# 002-0081_Rev_-.net
KiCad netlist of a schematic drawn in Altium Designer
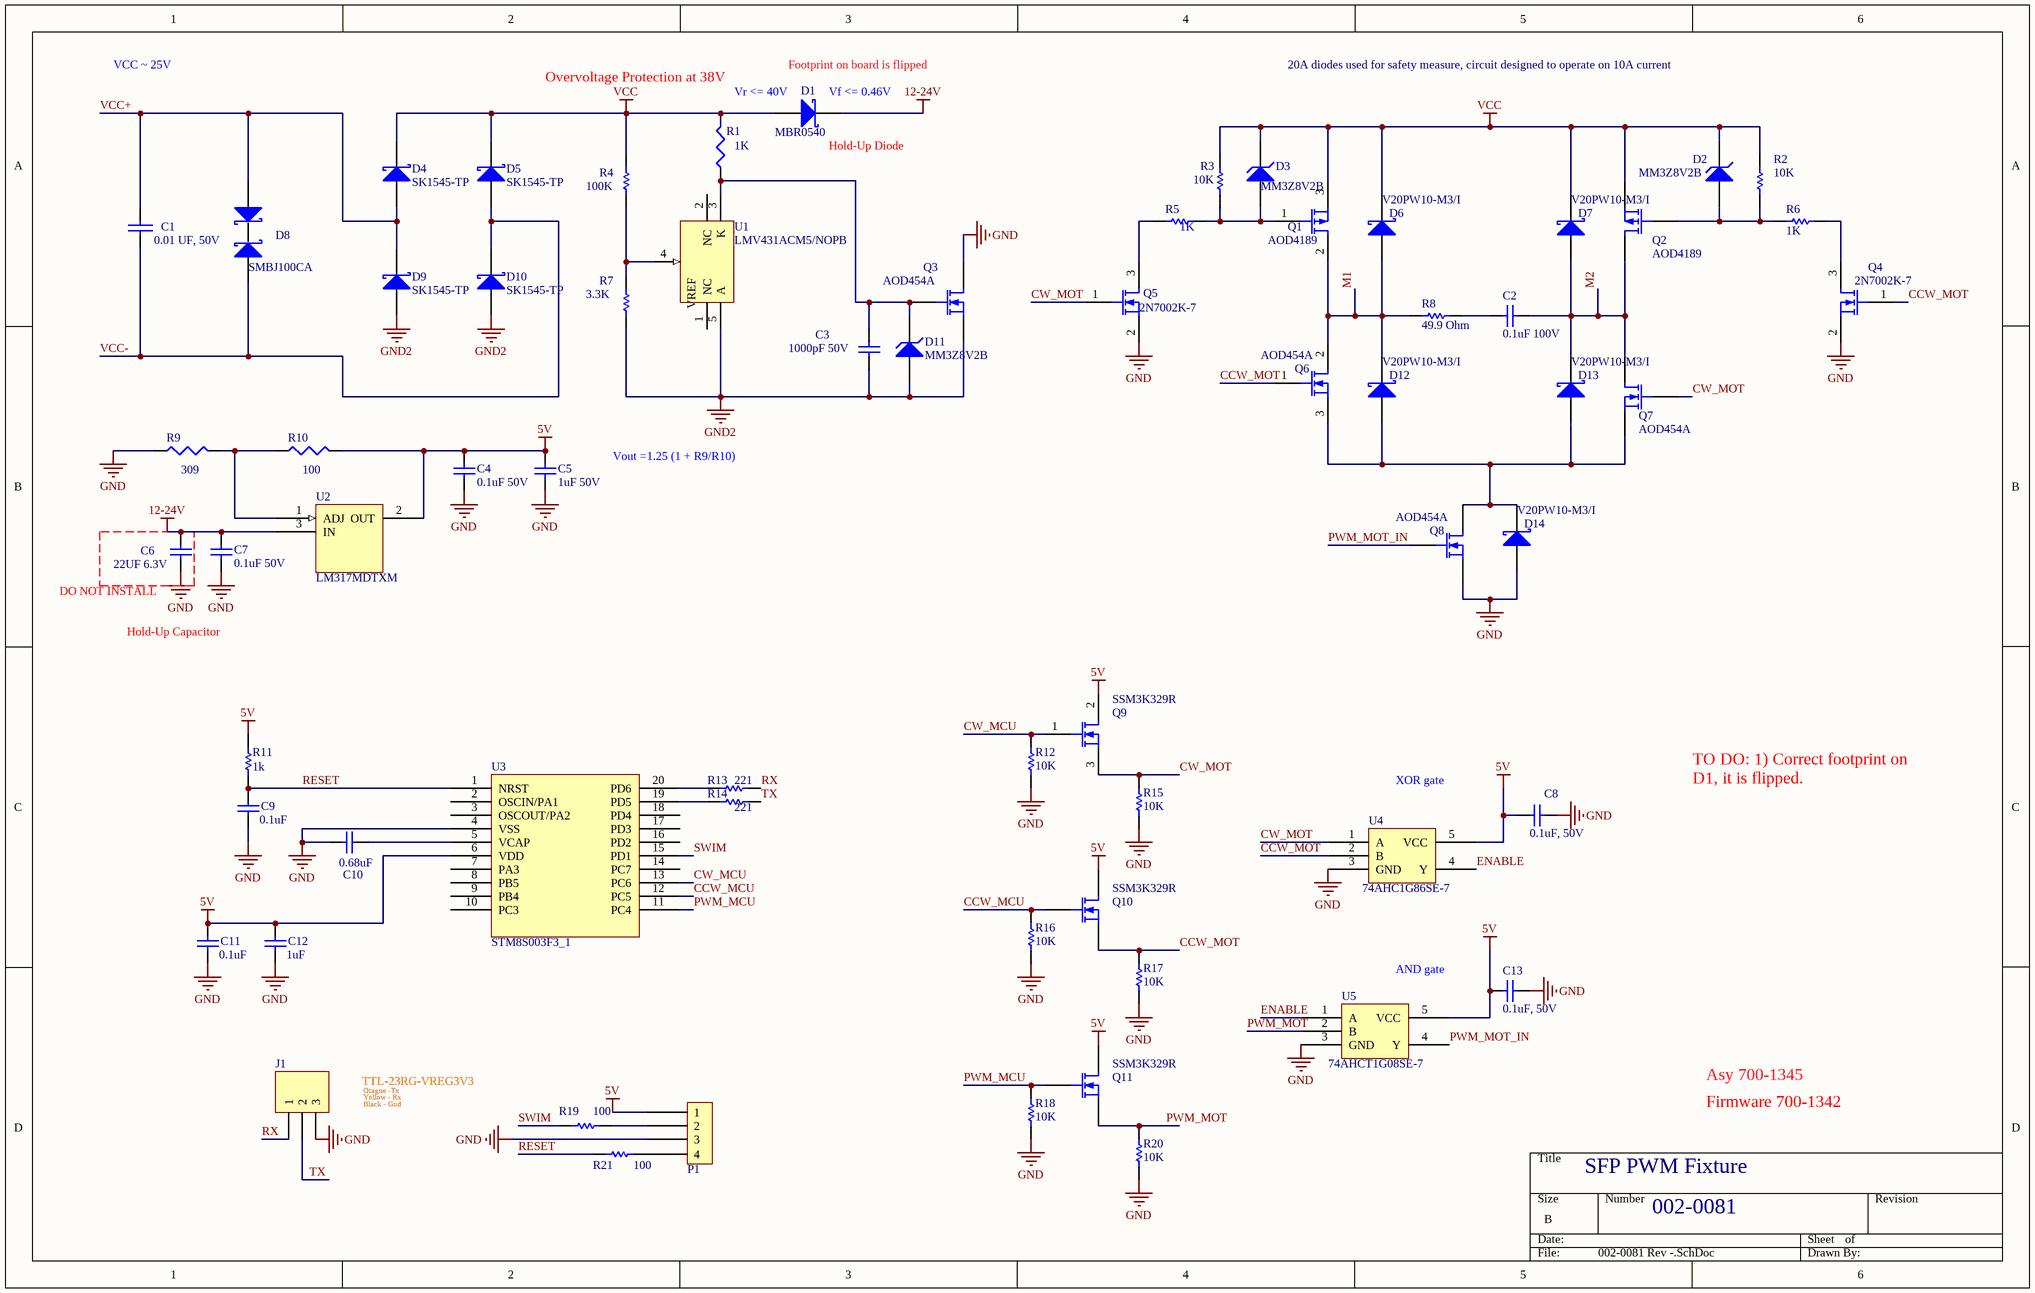
[diagram p0: 002-0081 Rev -.SchDoc]

(export (version "E")
  (design (tool "Eeschema 10.0.6"))
  (components
    (comp (ref "C1")
      (value "0.01 UF, 50V")
      (footprint "0603")
      (description "Cap Cer .01uf 50V 0603 RoHS")
      (fields
        (field (name "PEM PART NUMBER") "EE-1293")
        (field (name "MANUFACTURER") "Garrett Electronics Corporation")
      )
      (libsource (lib "*") (part "CAP"))
    )
    (comp (ref "C2")
      (value "0.1uF 100V")
      (footprint "RESC0805(2012)_N")
      (description "Cap Cer 0.1uF 100V 10% X7R 0805")
      (fields (field (name "PART NUMBER") "CL21B104KCFSFNE") (field (name "PEM PART NUMBER") "EE-1659"))
      (libsource (lib "Miscellaneous Devices") (part "Cap"))
    )
    (comp (ref "C3")
      (value "1000pF 50V")
      (footprint "0603")
      (description "CAP Cer, 0.1uF, 50V, 0603 X7R, 10%")
      (fields
        (field (name "MANUFACTURER PART NUMBER") "06035C104KAT2A")
        (field (name "PEM PART NUMBER") "EE-1343")
      )
      (libsource (lib "Miscellaneous Devices") (part "Cap"))
    )
    (comp (ref "C4")
      (value "0.1uF 50V")
      (footprint "0603")
      (description "CAP Cer, 0.1uF, 50V, 0603 X7R, 10%")
      (fields
        (field (name "MANUFACTURER PART NUMBER") "06035C104KAT2A")
        (field (name "PEM PART NUMBER") "EE-1425")
      )
      (libsource (lib "Miscellaneous Devices") (part "Cap"))
    )
    (comp (ref "C5")
      (value "1uF 50V")
      (footprint "0603")
      (description "CAP CER 1UF 50V 10% X5R 0603")
      (fields
        (field (name "MANUFACTURER PART NUMBER") "06035C104KAT2A")
        (field (name "PEM PART NUMBER") "EE-1708")
      )
      (libsource (lib "Miscellaneous Devices") (part "Cap"))
    )
    (comp (ref "C6")
      (value "22UF 6.3V")
      (footprint "0603")
      (description "CAP CER 22UF 6.3V X5R 0603")
      (fields
        (field (name "MANUFACTURER PART NUMBER") "06035C104KAT2A")
        (field (name "PEM PART NUMBER") "EE-1981")
      )
      (libsource (lib "Miscellaneous Devices") (part "Cap"))
    )
    (comp (ref "C7")
      (value "0.1uF 50V")
      (footprint "0603")
      (description "CAP Cer, 0.1uF, 50V, 0603 X7R, 10%")
      (fields
        (field (name "MANUFACTURER PART NUMBER") "06035C104KAT2A")
        (field (name "PEM PART NUMBER") "EE-1425")
      )
      (libsource (lib "Miscellaneous Devices") (part "Cap"))
    )
    (comp (ref "C8")
      (value "0.1uF, 50V")
      (footprint "0603")
      (description "CAP Cer, 0.1uF, 50V, 0603 X7R, 10%")
      (fields (field (name "PEM PART NUMBER") "EE-1425") (field (name "PART NUMBER") "06035C104KAT2A"))
      (libsource (lib "Miscellaneous Devices") (part "Cap"))
    )
    (comp (ref "C9")
      (value "0.1uF")
      (footprint "CAPC0402(1005)60_M")
      (description "Cap Cer 0.1uF 10V 10% X5R 0402")
      (fields (field (name "PART NUMBER") "LMK105BJ104KV-F") (field (name "PEM PART NUMBER") "EE-1661"))
      (libsource (lib "Miscellaneous Devices") (part "Cap"))
    )
    (comp (ref "C10")
      (value "0.68uF")
      (footprint "CAPC0402(1005)60_M")
      (description "Cap cer 0.68uF 6.3V 5% X6S 0402")
      (fields (field (name "PEM PART NUMBER") "EE-1673") (field (name "PART NUMBER") "CL05X684JQ5NNNC"))
      (libsource (lib "Miscellaneous Devices") (part "Cap"))
    )
    (comp (ref "C11")
      (value "0.1uF")
      (footprint "CAPC0402(1005)60_M")
      (description "Cap Cer 0.1uF 10V 10% X5R 0402")
      (fields (field (name "PART NUMBER") "LMK105BJ104KV-F") (field (name "PEM PART NUMBER") "EE-1661"))
      (libsource (lib "Miscellaneous Devices") (part "Cap"))
    )
    (comp (ref "C12")
      (value "1uF")
      (footprint "CAPC0402(1005)60_M")
      (description "Cap Cer 1uF 10V 10% X5R 0402")
      (fields (field (name "PART NUMBER") "C1005X5R1V105M050BC") (field (name "PEM PART NUMBER") "EE-1725"))
      (libsource (lib "Miscellaneous Devices") (part "Cap"))
    )
    (comp (ref "C13")
      (value "0.1uF, 50V")
      (footprint "0603")
      (description "Cap Cer 0.1uF 10V 10% X5R 0402")
      (fields (field (name "PEM PART NUMBER") "EE-1425") (field (name "PART NUMBER") "06035C104KAT2A"))
      (libsource (lib "Miscellaneous Devices") (part "Cap"))
    )
    (comp (ref "D1")
      (value "MBR0540")
      (footprint "SOD123/X.85")
      (description "Diode Schottky 40V 500ma SOD-123")
      (fields
        (field (name "MANUFACTURER PART NUMBER") "MBR0540-TP")
        (field (name "PEM PART NUMBER") "EE-1290")
      )
      (libsource (lib "Miscellaneous Devices") (part "D Schottky"))
    )
    (comp (ref "D2")
      (value "MM3Z8V2B")
      (footprint "SOD-323F")
      (description "DIODE ZENER 8.2V 200MW SOD323F")
      (fields (field (name "PEM PART NUMBER") "EE-1681"))
      (libsource (lib "Miscellaneous Devices") (part "D Zener"))
    )
    (comp (ref "D3")
      (value "MM3Z8V2B")
      (footprint "SOD-323F")
      (description "DIODE ZENER 8.2V 200MW SOD323F")
      (fields (field (name "PEM PART NUMBER") "EE-1681"))
      (libsource (lib "Miscellaneous Devices") (part "D Zener"))
    )
    (comp (ref "D4")
      (value "SK1545-TP")
      (footprint "SMC")
      (description "DIODE SCHOTTKY 45V 15A DO214AB")
      (fields (field (name "PEM PART NUMBER") "EE-2167"))
      (libsource (lib "") (part "D Schottky_1"))
    )
    (comp (ref "D5")
      (value "SK1545-TP")
      (footprint "SMC")
      (description "DIODE SCHOTTKY 45V 15A DO214AB")
      (fields (field (name "PEM PART NUMBER") "EE-2167"))
      (libsource (lib "") (part "D Schottky_1"))
    )
    (comp (ref "D6")
      (value "V20PW10-M3/I")
      (footprint "DPAK (TO-252-3)")
      (description "DIODE SCHOTTKY 100V 20A SLIMDPAK")
      (fields (field (name "PEM PART NUMBER") "EE-2166"))
      (libsource (lib "") (part "D Schottky_1"))
    )
    (comp (ref "D7")
      (value "V20PW10-M3/I")
      (footprint "DPAK (TO-252-3)")
      (description "DIODE SCHOTTKY 100V 20A SLIMDPAK")
      (fields (field (name "PEM PART NUMBER") "EE-2166"))
      (libsource (lib "") (part "D Schottky_1"))
    )
    (comp (ref "D8")
      (value "TVS DIODE 28VWM 45.4VC SMB")
      (footprint "SMB - Bidirection")
      (description "TVS DIODE 100VWM 162VC DO214AA")
      (fields
        (field (name "PART NUMBER") "SMBJ100CA")
        (field (name "MANUFACTURER") "ON Semiconductor")
        (field (name "PEM PART NUMBER") "EE-1946")
      )
      (libsource (lib "002-0017 Rev H") (part "Dual Zener"))
    )
    (comp (ref "D9")
      (value "SK1545-TP")
      (footprint "SMC")
      (description "DIODE SCHOTTKY 45V 15A DO214AB")
      (fields (field (name "PEM PART NUMBER") "EE-2167"))
      (libsource (lib "") (part "D Schottky_1"))
    )
    (comp (ref "D10")
      (value "SK1545-TP")
      (footprint "SMC")
      (description "DIODE SCHOTTKY 45V 15A DO214AB")
      (fields (field (name "PEM PART NUMBER") "EE-2167"))
      (libsource (lib "") (part "D Schottky_1"))
    )
    (comp (ref "D11")
      (value "MM3Z8V2B")
      (footprint "SOD-323F")
      (description "DIODE ZENER 8.2V 200MW SOD323F")
      (fields (field (name "PEM PART NUMBER") "EE-1681"))
      (libsource (lib "Miscellaneous Devices") (part "D Zener"))
    )
    (comp (ref "D12")
      (value "V20PW10-M3/I")
      (footprint "DPAK (TO-252-3)")
      (description "DIODE SCHOTTKY 100V 20A SLIMDPAK")
      (fields (field (name "PEM PART NUMBER") "EE-2166"))
      (libsource (lib "") (part "D Schottky_1"))
    )
    (comp (ref "D13")
      (value "V20PW10-M3/I")
      (footprint "DPAK (TO-252-3)")
      (description "DIODE SCHOTTKY 100V 20A SLIMDPAK")
      (fields (field (name "PEM PART NUMBER") "EE-2166"))
      (libsource (lib "") (part "D Schottky_1"))
    )
    (comp (ref "D14")
      (value "V20PW10-M3/I")
      (footprint "DPAK (TO-252-3)")
      (description "DIODE SCHOTTKY 100V 20A SLIMDPAK")
      (fields (field (name "PEM PART NUMBER") "EE-2166"))
      (libsource (lib "") (part "D Schottky_1"))
    )
    (comp (ref "J1")
      (value "RS232 Conn")
      (footprint "SCON3/.10")
      (description "CONN HDR VERT 3POS .100 TIN")
      (fields
        (field (name "PEM PART NUMBER") "EE-1116")
        (field (name "MANUFACTURER") "Phoenix Contact")
        (field (name "PUBLISHER") "Altium Limited")
      )
      (libsource (lib "Miscellaneous Connectors") (part "Header 3"))
    )
    (comp (ref "P1")
      (value "4 Pin Connector")
      (footprint "4 PIN IN-LINE")
      (fields
        (field (name "PEM PART NUMBER") "EE-1855")
        (field (name "PART NUMBER") "GRPB501VWVN-RC")
        (field (name "MANUFACTURER") "Sullins Connector Solutions")
      )
      (libsource (lib "002 - 0053 Rev A") (part "4 Pin Connector"))
    )
    (comp (ref "Q1")
      (value "AOD4189")
      (footprint "DPAK (TO-252-3)")
      (description "MOSFET P-CH 40V 40A TO252 DPAK")
      (fields (field (name "PEM PART NUMBER") "EE-1879"))
      (libsource (lib "") (part "MOSFET-P_1"))
    )
    (comp (ref "Q2")
      (value "AOD4189")
      (footprint "DPAK (TO-252-3)")
      (description "MOSFET P-CH 40V 40A TO252 DPAK")
      (fields (field (name "PEM PART NUMBER") "EE-1879"))
      (libsource (lib "Miscellaneous Devices") (part "MOSFET-P"))
    )
    (comp (ref "Q3")
      (value "AOD454A")
      (footprint "DPAK (TO-252-3)")
      (description "MOSFET N-CH 250V 16A D-PAK")
      (fields (field (name "PEM PART NUMBER") "EE-1898"))
      (libsource (lib "") (part "MOSFET-N_1"))
    )
    (comp (ref "Q4")
      (value "2N7002K-7")
      (footprint "SOT-23-3")
      (description "MOSFET N-CH 60V 0.38A SOT23-3")
      (fields (field (name "PEM PART NUMBER") "EE-2053"))
      (libsource (lib "") (part "MOSFET-N_2"))
    )
    (comp (ref "Q5")
      (value "2N7002K-7")
      (footprint "SOT-23-3")
      (description "MOSFET N-CH 60V 0.38A SOT23-3")
      (fields (field (name "PEM PART NUMBER") "EE-2053"))
      (libsource (lib "") (part "MOSFET-N_2"))
    )
    (comp (ref "Q6")
      (value "AOD454A")
      (footprint "DPAK (TO-252-3)")
      (description "MOSFET N-CH 40V 20A TO252")
      (fields
        (field (name "MANUFACTURER") "Alpha & Omega Semiconductor Inc.")
        (field (name "PEM PART NUMBER") "EE-1898")
      )
      (libsource (lib "Miscellaneous Devices") (part "MOSFET-N"))
    )
    (comp (ref "Q7")
      (value "AOD454A")
      (footprint "DPAK (TO-252-3)")
      (description "MOSFET N-CH 40V 20A TO252")
      (fields
        (field (name "MANUFACTURER") "Alpha & Omega Semiconductor Inc.")
        (field (name "PEM PART NUMBER") "EE-1898")
      )
      (libsource (lib "") (part "MOSFET-N_1"))
    )
    (comp (ref "Q8")
      (value "AOD454A")
      (footprint "DPAK (TO-252-3)")
      (description "MOSFET N-CH 40V 20A TO252")
      (fields
        (field (name "MANUFACTURER") "Alpha & Omega Semiconductor Inc.")
        (field (name "PEM PART NUMBER") "EE-1898")
      )
      (libsource (lib "") (part "MOSFET-N_1"))
    )
    (comp (ref "Q9")
      (value "SSM3K329R")
      (footprint "SOT-23F")
      (description "N-Channel 30V 3.5A (Ta) 1W (Ta) Surface Mount SOT-23F")
      (fields
        (field (name "MANUFACTURER") "Alpha & Omega Semiconductor Inc.")
        (field (name "PEM PART NUMBER") "EE-1830")
      )
      (libsource (lib "Miscellaneous Devices") (part "MOSFET-N"))
    )
    (comp (ref "Q10")
      (value "SSM3K329R")
      (footprint "SOT-23F")
      (description "N-Channel 30V 3.5A (Ta) 1W (Ta) Surface Mount SOT-23F")
      (fields
        (field (name "MANUFACTURER") "Alpha & Omega Semiconductor Inc.")
        (field (name "PEM PART NUMBER") "EE-1830")
      )
      (libsource (lib "") (part "MOSFET-N_1"))
    )
    (comp (ref "Q11")
      (value "SSM3K329R")
      (footprint "SOT-23F")
      (description "N-Channel 30V 3.5A (Ta) 1W (Ta) Surface Mount SOT-23F")
      (fields
        (field (name "PART NUMBER") "AOD454A")
        (field (name "MANUFACTURER") "Alpha & Omega Semiconductor Inc.")
      )
      (libsource (lib "") (part "MOSFET-N_1"))
    )
    (comp (ref "R1")
      (value "1K")
      (footprint "002-0081 Rev -:RESC0603(1608)_M")
      (description "RES SMD 1K OHM 1% 1/10W 0603")
      (fields
        (field (name "PEM PART NUMBER") "EE-2066")
        (field (name "Comment") "Res3")
        (field (name "PUBLISHER") "Altium Limited")
      )
      (libsource (lib "Miscellaneous Devices") (part "Res3"))
    )
    (comp (ref "R2")
      (value "10K")
      (footprint "RESC0603(1608)_M")
      (description "Res 10K 0603 1% 1/10W RoHS")
      (fields (field (name "PART NUMBER") "RK73H1JTTD1002F") (field (name "PEM PART NUMBER") "EE-1296"))
      (libsource (lib "Miscellaneous Devices") (part "Res1"))
    )
    (comp (ref "R3")
      (value "10K")
      (footprint "RESC0603(1608)_M")
      (description "Res 10K 0603 1% 1/10W RoHS")
      (fields (field (name "PART NUMBER") "RK73H1JTTD1002F") (field (name "PEM PART NUMBER") "EE-1296"))
      (libsource (lib "Miscellaneous Devices") (part "Res1"))
    )
    (comp (ref "R4")
      (value "100K")
      (footprint "RESC0603(1608)_M")
      (description "Res 100K 0603 1% 1/10W RoHS")
      (fields (field (name "PART NUMBER") "RK73H1JTTD1002F") (field (name "PEM PART NUMBER") "EE-1295"))
      (libsource (lib "Miscellaneous Devices") (part "Res1"))
    )
    (comp (ref "R5")
      (value "1K")
      (footprint "RESC0603(1608)_M")
      (description "Res 1.0K 0603 1% 1/10W RoHS")
      (fields
        (field (name "MANUFACTURER PART NUMBER") "CRCW06031K00FKEA")
        (field (name "PEM PART NUMBER") "EE-1297")
      )
      (libsource (lib "Miscellaneous Devices") (part "Res1"))
    )
    (comp (ref "R6")
      (value "1K")
      (footprint "RESC0603(1608)_M")
      (description "Res 1.0K 0603 1% 1/10W RoHS")
      (fields
        (field (name "MANUFACTURER PART NUMBER") "CRCW06031K00FKEA")
        (field (name "PEM PART NUMBER") "EE-1297")
      )
      (libsource (lib "Miscellaneous Devices") (part "Res1"))
    )
    (comp (ref "R7")
      (value "3.3K")
      (footprint "RESC0603(1608)_M")
      (description "RES 23.7K OHM 1/10W 1% 0603 SMD")
      (fields (field (name "PART NUMBER") "MCR03ERTF3301") (field (name "PEM PART NUMBER") "EE-1730"))
      (libsource (lib "Miscellaneous Devices") (part "Res1"))
    )
    (comp (ref "R8")
      (value "49.9 Ohm")
      (footprint "RESC0805(2012)_N")
      (description "Res 49.9R 0805 1% 1/8W")
      (fields (field (name "PEM PART NUMBER") "EE-1238") (field (name "PART NUMBER") "9C08052A49R9FKHFT"))
      (libsource (lib "Miscellaneous Devices") (part "Res1"))
    )
    (comp (ref "R9")
      (value "309")
      (footprint "J1-0603")
      (description "Res 10K 0603 1% 1/10W RoHS")
      (fields (field (name "PEM PART NUMBER") "EE-1296") (field (name "PART NUMBER") "RK73H1JTTD1002F"))
      (libsource (lib "Miscellaneous Devices") (part "Res3"))
    )
    (comp (ref "R10")
      (value "100")
      (footprint "J1-0603")
      (description "Res 3.3K 0603 1% 1/8W RoHS")
      (fields (field (name "PEM PART NUMBER") "EE-1730") (field (name "PART NUMBER") "MCR03ERTF3301"))
      (libsource (lib "Miscellaneous Devices") (part "Res3"))
    )
    (comp (ref "R11")
      (value "1k")
      (footprint "RESC0402(1005)_N")
      (description "Res 1K 0402 1% 1/16W RoHS")
      (fields (field (name "PEM PART NUMBER") "EE-1581") (field (name "PART NUMBER") "CRCW04021K00FKED"))
      (libsource (lib "Miscellaneous Devices") (part "Res1"))
    )
    (comp (ref "R12")
      (value "10K")
      (footprint "RESC0603(1608)_M")
      (description "Res 10K 0603 1% 1/10W RoHS")
      (fields (field (name "PART NUMBER") "RK73H1JTTD1002F") (field (name "PEM PART NUMBER") "EE-1296"))
      (libsource (lib "Miscellaneous Devices") (part "Res1"))
    )
    (comp (ref "R13")
      (value "221")
      (footprint "RESC0402(1005)_N")
      (description "RES SMD 221 OHM 1% 1/16W 0402")
      (fields (field (name "PART NUMBER") "RC1005F2210CS") (field (name "PEM PART NUMBER") "EE-1798"))
      (libsource (lib "Miscellaneous Devices") (part "Res1"))
    )
    (comp (ref "R14")
      (value "221")
      (footprint "RESC0402(1005)_N")
      (description "Res 1K 0603 1% 1/10W RoHS")
      (fields (field (name "PART NUMBER") "RC1005F2210CS") (field (name "PEM PART NUMBER") "EE-1798"))
      (libsource (lib "Miscellaneous Devices") (part "Res1"))
    )
    (comp (ref "R15")
      (value "10K")
      (footprint "RESC0603(1608)_M")
      (description "Res 10K 0603 1% 1/10W RoHS")
      (fields (field (name "PART NUMBER") "RK73H1JTTD1002F") (field (name "PEM PART NUMBER") "EE-1296"))
      (libsource (lib "Miscellaneous Devices") (part "Res1"))
    )
    (comp (ref "R16")
      (value "10K")
      (footprint "RESC0603(1608)_M")
      (description "Res 10K 0603 1% 1/10W RoHS")
      (fields (field (name "PART NUMBER") "RK73H1JTTD1002F") (field (name "PEM PART NUMBER") "EE-1296"))
      (libsource (lib "Miscellaneous Devices") (part "Res1"))
    )
    (comp (ref "R17")
      (value "10K")
      (footprint "RESC0603(1608)_M")
      (description "Res 10K 0603 1% 1/10W RoHS")
      (fields (field (name "PART NUMBER") "RK73H1JTTD1002F") (field (name "PEM PART NUMBER") "EE-1296"))
      (libsource (lib "Miscellaneous Devices") (part "Res1"))
    )
    (comp (ref "R18")
      (value "10K")
      (footprint "RESC0603(1608)_M")
      (description "Res 10K 0603 1% 1/10W RoHS")
      (fields (field (name "PART NUMBER") "RK73H1JTTD1002F") (field (name "PEM PART NUMBER") "EE-1296"))
      (libsource (lib "Miscellaneous Devices") (part "Res1"))
    )
    (comp (ref "R19")
      (value "100")
      (footprint "RESC0402(1005)_N")
      (description "Res 100R 0402 1% 1/16W RoHs")
      (fields (field (name "PEM PART NUMBER") "EE-1588") (field (name "PART NUMBER") "RC0402FR-07100RL"))
      (libsource (lib "Miscellaneous Devices") (part "Res1"))
    )
    (comp (ref "R20")
      (value "10K")
      (footprint "RESC0603(1608)_M")
      (description "Res 10K 0603 1% 1/10W RoHS")
      (fields (field (name "PART NUMBER") "RK73H1JTTD1002F") (field (name "PEM PART NUMBER") "EE-1296"))
      (libsource (lib "Miscellaneous Devices") (part "Res1"))
    )
    (comp (ref "R21")
      (value "100")
      (footprint "RESC0402(1005)_N")
      (description "Res 100R 0402 1% 1/16W RoHs")
      (fields (field (name "PEM PART NUMBER") "EE-1588") (field (name "PART NUMBER") "RC0402FR-07100RL"))
      (libsource (lib "Miscellaneous Devices") (part "Res1"))
    )
    (comp (ref "U1")
      (value "LMV431ACM5/NOPB")
      (footprint "DBV005")
      (description "IC VREF SHUNT ADJ SOT23-5")
      (fields (field (name "PEM PART NUMBER") "EE-1900"))
      (libsource (lib "TI Power Mgt Voltage Regulator") (part "TL431IDBVR"))
    )
    (comp (ref "U2")
      (value "LM317MDTXM")
      (footprint "DPAK (TO-252-3)")
      (description "SMT, IC, Adjust Voltage Reg, 0.5A, 3TERM, TO-252, 40V diff max")
      (fields
        (field (name "PEM PART NUMBER") "EE-1248")
        (field (name "MANUFACTURER") "Fairchild Semiconductor")
      )
      (libsource (lib "*") (part "LM317D2T(3)"))
    )
    (comp (ref "U3")
      (value "STM8S003F3_1")
      (footprint "UFQFPN20_V")
      (description "MCU 8BIT 8KB 16MHZ 20-UFQFPN")
      (fields (field (name "PEM PART NUMBER") "EE-1655") (field (name "PART NUMBER") "STM8S003F3U6TR"))
      (libsource (lib "SlowActuator") (part "STM8S003F3_1"))
    )
    (comp (ref "U4")
      (value "74AHC1G86SE-7")
      (footprint "SOT-353")
      (description "IC GATE XOR 1CH 2-INP SOT353")
      (fields (field (name "PEM PART NUMBER") "EE-2165") (field (name "MANUFACTURER") "Diodes Incorporated"))
      (libsource (lib "002-0066 Rev -") (part "NC7SZ08"))
    )
    (comp (ref "U5")
      (value "74AHCT1G08SE-7")
      (footprint "SOT-353")
      (description "IC GATE AND 1CH 2-INP SOT-353")
      (fields (field (name "PEM PART NUMBER") "EE-1801") (field (name "MANUFACTURER") "Diodes Incorporated"))
      (libsource (lib "002-0066 Rev -") (part "NC7SZ08"))
    )
  )
  (nets
    (net (code "1") (name "/CCW_MCU") (class "Default")
      (node (ref "Q10") (pin "1") (pinfunction "G_1") (pintype "passive"))
      (node (ref "R16") (pin "1") (pinfunction "1_1") (pintype "passive"))
      (node (ref "U3") (pin "12") (pinfunction "PC5_12") (pintype "passive"))
    )
    (net (code "2") (name "/CCW_MOT") (class "Default")
      (node (ref "Q10") (pin "3") (pinfunction "S_3") (pintype "passive"))
      (node (ref "Q4") (pin "1") (pinfunction "G_1") (pintype "passive"))
      (node (ref "Q6") (pin "1") (pinfunction "G_1") (pintype "passive"))
      (node (ref "R17") (pin "1") (pinfunction "1_1") (pintype "passive"))
      (node (ref "U4") (pin "2") (pinfunction "B_2") (pintype "passive"))
    )
    (net (code "3") (name "/CW_MCU") (class "Default")
      (node (ref "Q9") (pin "1") (pinfunction "G_1") (pintype "passive"))
      (node (ref "R12") (pin "1") (pinfunction "1_1") (pintype "passive"))
      (node (ref "U3") (pin "13") (pinfunction "PC6_13") (pintype "passive"))
    )
    (net (code "4") (name "/CW_MOT") (class "Default")
      (node (ref "Q5") (pin "1") (pinfunction "G_1") (pintype "passive"))
      (node (ref "Q7") (pin "1") (pinfunction "G_1") (pintype "passive"))
      (node (ref "Q9") (pin "3") (pinfunction "S_3") (pintype "passive"))
      (node (ref "R15") (pin "1") (pinfunction "1_1") (pintype "passive"))
      (node (ref "U4") (pin "1") (pinfunction "A_1") (pintype "passive"))
    )
    (net (code "5") (name "/ENABLE") (class "Default")
      (node (ref "U4") (pin "4") (pinfunction "Y_4") (pintype "passive"))
      (node (ref "U5") (pin "1") (pinfunction "A_1") (pintype "passive"))
    )
    (net (code "6") (name "/M1") (class "Default")
      (node (ref "D12") (pin "2") (pinfunction "K_2") (pintype "passive"))
      (node (ref "D6") (pin "1") (pinfunction "A_1") (pintype "passive"))
      (node (ref "Q1") (pin "2") (pinfunction "D_2") (pintype "passive"))
      (node (ref "Q6") (pin "2") (pinfunction "D_2") (pintype "passive"))
      (node (ref "R8") (pin "2") (pinfunction "2_2") (pintype "passive"))
    )
    (net (code "7") (name "/M2") (class "Default")
      (node (ref "C2") (pin "1") (pinfunction "1_1") (pintype "passive"))
      (node (ref "D13") (pin "2") (pinfunction "K_2") (pintype "passive"))
      (node (ref "D7") (pin "1") (pinfunction "A_1") (pintype "passive"))
      (node (ref "Q2") (pin "2") (pinfunction "D_2") (pintype "passive"))
      (node (ref "Q7") (pin "2") (pinfunction "D_2") (pintype "passive"))
    )
    (net (code "8") (name "/PWM_MCU") (class "Default")
      (node (ref "Q11") (pin "1") (pinfunction "G_1") (pintype "passive"))
      (node (ref "R18") (pin "1") (pinfunction "1_1") (pintype "passive"))
      (node (ref "U3") (pin "11") (pinfunction "PC4_11") (pintype "passive"))
    )
    (net (code "9") (name "/PWM_MOT") (class "Default")
      (node (ref "Q11") (pin "3") (pinfunction "S_3") (pintype "passive"))
      (node (ref "R20") (pin "1") (pinfunction "1_1") (pintype "passive"))
      (node (ref "U5") (pin "2") (pinfunction "B_2") (pintype "passive"))
    )
    (net (code "10") (name "/PWM_MOT_IN") (class "Default")
      (node (ref "Q8") (pin "1") (pinfunction "G_1") (pintype "passive"))
      (node (ref "U5") (pin "4") (pinfunction "Y_4") (pintype "passive"))
    )
    (net (code "11") (name "/RESET") (class "Default")
      (node (ref "C9") (pin "2") (pinfunction "2_2") (pintype "passive"))
      (node (ref "R11") (pin "1") (pinfunction "1_1") (pintype "passive"))
      (node (ref "R21") (pin "1") (pinfunction "1_1") (pintype "passive"))
      (node (ref "U3") (pin "1") (pinfunction "NRST_1") (pintype "passive"))
    )
    (net (code "12") (name "/RX") (class "Default")
      (node (ref "J1") (pin "1") (pinfunction "1_1") (pintype "passive"))
      (node (ref "R13") (pin "2") (pinfunction "2_2") (pintype "passive"))
    )
    (net (code "13") (name "/SWIM") (class "Default")
      (node (ref "R19") (pin "1") (pinfunction "1_1") (pintype "passive"))
      (node (ref "U3") (pin "15") (pinfunction "PD1_15") (pintype "passive"))
    )
    (net (code "14") (name "/TX") (class "Default")
      (node (ref "J1") (pin "2") (pinfunction "2_2") (pintype "passive"))
      (node (ref "R14") (pin "2") (pinfunction "2_2") (pintype "passive"))
    )
    (net (code "15") (name "/VCC+") (class "Default")
      (node (ref "C1") (pin "1") (pinfunction "1_1") (pintype "passive"))
      (node (ref "D4") (pin "1") (pinfunction "A_1") (pintype "passive"))
      (node (ref "D8") (pin "2") (pinfunction "2_2") (pintype "passive"))
      (node (ref "D9") (pin "2") (pinfunction "K_2") (pintype "passive"))
    )
    (net (code "16") (name "/VCC-") (class "Default")
      (node (ref "C1") (pin "2") (pinfunction "2_2") (pintype "passive"))
      (node (ref "D10") (pin "2") (pinfunction "K_2") (pintype "passive"))
      (node (ref "D5") (pin "1") (pinfunction "A_1") (pintype "passive"))
      (node (ref "D8") (pin "1") (pinfunction "1_1") (pintype "passive"))
    )
    (net (code "17") (name "5V") (class "Default")
      (node (ref "C11") (pin "2") (pinfunction "2_2") (pintype "passive"))
      (node (ref "C12") (pin "2") (pinfunction "2_2") (pintype "passive"))
      (node (ref "C13") (pin "2") (pinfunction "2_2") (pintype "passive"))
      (node (ref "C4") (pin "2") (pinfunction "2_2") (pintype "passive"))
      (node (ref "C5") (pin "2") (pinfunction "2_2") (pintype "passive"))
      (node (ref "C8") (pin "2") (pinfunction "2_2") (pintype "passive"))
      (node (ref "P1") (pin "1") (pinfunction "1_1") (pintype "passive"))
      (node (ref "Q10") (pin "2") (pinfunction "D_2") (pintype "passive"))
      (node (ref "Q11") (pin "2") (pinfunction "D_2") (pintype "passive"))
      (node (ref "Q9") (pin "2") (pinfunction "D_2") (pintype "passive"))
      (node (ref "R10") (pin "2") (pinfunction "2_2") (pintype "passive"))
      (node (ref "R11") (pin "2") (pinfunction "2_2") (pintype "passive"))
      (node (ref "U2") (pin "2") (pinfunction "OUT_2") (pintype "power_in"))
      (node (ref "U3") (pin "6") (pinfunction "VDD_6") (pintype "passive"))
      (node (ref "U4") (pin "5") (pinfunction "VCC_5") (pintype "passive"))
      (node (ref "U5") (pin "5") (pinfunction "VCC_5") (pintype "passive"))
    )
    (net (code "18") (name "12-24V") (class "Default")
      (node (ref "C6") (pin "2") (pinfunction "2_2") (pintype "passive"))
      (node (ref "C7") (pin "2") (pinfunction "2_2") (pintype "passive"))
      (node (ref "D1") (pin "1") (pinfunction "K_1") (pintype "passive"))
      (node (ref "U2") (pin "3") (pinfunction "IN_3") (pintype "power_in"))
    )
    (net (code "19") (name "GND") (class "Default")
      (node (ref "C10") (pin "1") (pinfunction "1_1") (pintype "passive"))
      (node (ref "C11") (pin "1") (pinfunction "1_1") (pintype "passive"))
      (node (ref "C12") (pin "1") (pinfunction "1_1") (pintype "passive"))
      (node (ref "C13") (pin "1") (pinfunction "1_1") (pintype "passive"))
      (node (ref "C4") (pin "1") (pinfunction "1_1") (pintype "passive"))
      (node (ref "C5") (pin "1") (pinfunction "1_1") (pintype "passive"))
      (node (ref "C6") (pin "1") (pinfunction "1_1") (pintype "passive"))
      (node (ref "C7") (pin "1") (pinfunction "1_1") (pintype "passive"))
      (node (ref "C8") (pin "1") (pinfunction "1_1") (pintype "passive"))
      (node (ref "C9") (pin "1") (pinfunction "1_1") (pintype "passive"))
      (node (ref "D14") (pin "1") (pinfunction "A_1") (pintype "passive"))
      (node (ref "J1") (pin "3") (pinfunction "3_3") (pintype "passive"))
      (node (ref "P1") (pin "3") (pinfunction "3_3") (pintype "passive"))
      (node (ref "Q3") (pin "2") (pinfunction "D_2") (pintype "passive"))
      (node (ref "Q4") (pin "2") (pinfunction "S_2") (pintype "passive"))
      (node (ref "Q5") (pin "2") (pinfunction "S_2") (pintype "passive"))
      (node (ref "Q8") (pin "3") (pinfunction "S_3") (pintype "passive"))
      (node (ref "R12") (pin "2") (pinfunction "2_2") (pintype "passive"))
      (node (ref "R15") (pin "2") (pinfunction "2_2") (pintype "passive"))
      (node (ref "R16") (pin "2") (pinfunction "2_2") (pintype "passive"))
      (node (ref "R17") (pin "2") (pinfunction "2_2") (pintype "passive"))
      (node (ref "R18") (pin "2") (pinfunction "2_2") (pintype "passive"))
      (node (ref "R20") (pin "2") (pinfunction "2_2") (pintype "passive"))
      (node (ref "R9") (pin "1") (pinfunction "1_1") (pintype "passive"))
      (node (ref "U3") (pin "4") (pinfunction "VSS_4") (pintype "passive"))
      (node (ref "U4") (pin "3") (pinfunction "GND_3") (pintype "passive"))
      (node (ref "U5") (pin "3") (pinfunction "GND_3") (pintype "passive"))
    )
    (net (code "20") (name "GND2") (class "Default")
      (node (ref "C3") (pin "1") (pinfunction "1_1") (pintype "passive"))
      (node (ref "D10") (pin "1") (pinfunction "A_1") (pintype "passive"))
      (node (ref "D11") (pin "1") (pinfunction "A_1") (pintype "passive"))
      (node (ref "D9") (pin "1") (pinfunction "A_1") (pintype "passive"))
      (node (ref "Q3") (pin "3") (pinfunction "S_3") (pintype "passive"))
      (node (ref "R7") (pin "2") (pinfunction "2_2") (pintype "passive"))
      (node (ref "U1") (pin "5") (pinfunction "A_5") (pintype "power_in"))
    )
    (net (code "21") (name "Net-(C2-Pad2)") (class "Default")
      (node (ref "C2") (pin "2") (pinfunction "2_2") (pintype "passive"))
      (node (ref "R8") (pin "1") (pinfunction "1_1") (pintype "passive"))
    )
    (net (code "22") (name "Net-(D2-A)") (class "Default")
      (node (ref "D2") (pin "1") (pinfunction "A_1") (pintype "passive"))
      (node (ref "Q2") (pin "1") (pinfunction "G_1") (pintype "passive"))
      (node (ref "R2") (pin "2") (pinfunction "2_2") (pintype "passive"))
      (node (ref "R6") (pin "1") (pinfunction "1_1") (pintype "passive"))
    )
    (net (code "23") (name "Net-(D3-A)") (class "Default")
      (node (ref "D3") (pin "1") (pinfunction "A_1") (pintype "passive"))
      (node (ref "Q1") (pin "1") (pinfunction "G_1") (pintype "passive"))
      (node (ref "R3") (pin "2") (pinfunction "2_2") (pintype "passive"))
      (node (ref "R5") (pin "2") (pinfunction "2_2") (pintype "passive"))
    )
    (net (code "24") (name "Net-(D11-K)") (class "Default")
      (node (ref "C3") (pin "2") (pinfunction "2_2") (pintype "passive"))
      (node (ref "D11") (pin "2") (pinfunction "K_2") (pintype "passive"))
      (node (ref "Q3") (pin "1") (pinfunction "G_1") (pintype "passive"))
      (node (ref "R1") (pin "1") (pinfunction "1_1") (pintype "passive"))
      (node (ref "U1") (pin "3") (pinfunction "K_3") (pintype "power_in"))
    )
    (net (code "25") (name "Net-(D12-A)") (class "Default")
      (node (ref "D12") (pin "1") (pinfunction "A_1") (pintype "passive"))
      (node (ref "D13") (pin "1") (pinfunction "A_1") (pintype "passive"))
      (node (ref "D14") (pin "2") (pinfunction "K_2") (pintype "passive"))
      (node (ref "Q6") (pin "3") (pinfunction "S_3") (pintype "passive"))
      (node (ref "Q7") (pin "3") (pinfunction "S_3") (pintype "passive"))
      (node (ref "Q8") (pin "2") (pinfunction "D_2") (pintype "passive"))
    )
    (net (code "26") (name "Net-(P1-Pad2)") (class "Default")
      (node (ref "P1") (pin "2") (pinfunction "2_2") (pintype "passive"))
      (node (ref "R19") (pin "2") (pinfunction "2_2") (pintype "passive"))
    )
    (net (code "27") (name "Net-(P1-Pad4)") (class "Default")
      (node (ref "P1") (pin "4") (pinfunction "4_4") (pintype "passive"))
      (node (ref "R21") (pin "2") (pinfunction "2_2") (pintype "passive"))
    )
    (net (code "28") (name "Net-(Q4-D)") (class "Default")
      (node (ref "Q4") (pin "3") (pinfunction "D_3") (pintype "passive"))
      (node (ref "R6") (pin "2") (pinfunction "2_2") (pintype "passive"))
    )
    (net (code "29") (name "Net-(Q5-D)") (class "Default")
      (node (ref "Q5") (pin "3") (pinfunction "D_3") (pintype "passive"))
      (node (ref "R5") (pin "1") (pinfunction "1_1") (pintype "passive"))
    )
    (net (code "30") (name "Net-(U1-REF)") (class "Default")
      (node (ref "R4") (pin "2") (pinfunction "2_2") (pintype "passive"))
      (node (ref "R7") (pin "1") (pinfunction "1_1") (pintype "passive"))
      (node (ref "U1") (pin "4") (pinfunction "REF_4") (pintype "input"))
    )
    (net (code "31") (name "Net-(U2-ADJ)") (class "Default")
      (node (ref "R10") (pin "1") (pinfunction "1_1") (pintype "passive"))
      (node (ref "R9") (pin "2") (pinfunction "2_2") (pintype "passive"))
      (node (ref "U2") (pin "1") (pinfunction "ADJ_1") (pintype "input"))
    )
    (net (code "32") (name "Net-(U3-PD5)") (class "Default")
      (node (ref "R14") (pin "1") (pinfunction "1_1") (pintype "passive"))
      (node (ref "U3") (pin "19") (pinfunction "PD5_19") (pintype "passive"))
    )
    (net (code "33") (name "Net-(U3-PD6)") (class "Default")
      (node (ref "R13") (pin "1") (pinfunction "1_1") (pintype "passive"))
      (node (ref "U3") (pin "20") (pinfunction "PD6_20") (pintype "passive"))
    )
    (net (code "34") (name "Net-(U3-VCAP)") (class "Default")
      (node (ref "C10") (pin "2") (pinfunction "2_2") (pintype "passive"))
      (node (ref "U3") (pin "5") (pinfunction "VCAP_5") (pintype "passive"))
    )
    (net (code "35") (name "VCC") (class "Default")
      (node (ref "D1") (pin "2") (pinfunction "A_2") (pintype "passive"))
      (node (ref "D2") (pin "2") (pinfunction "K_2") (pintype "passive"))
      (node (ref "D3") (pin "2") (pinfunction "K_2") (pintype "passive"))
      (node (ref "D4") (pin "2") (pinfunction "K_2") (pintype "passive"))
      (node (ref "D5") (pin "2") (pinfunction "K_2") (pintype "passive"))
      (node (ref "D6") (pin "2") (pinfunction "K_2") (pintype "passive"))
      (node (ref "D7") (pin "2") (pinfunction "K_2") (pintype "passive"))
      (node (ref "Q1") (pin "3") (pinfunction "S_3") (pintype "passive"))
      (node (ref "Q2") (pin "3") (pinfunction "S_3") (pintype "passive"))
      (node (ref "R1") (pin "2") (pinfunction "2_2") (pintype "passive"))
      (node (ref "R2") (pin "1") (pinfunction "1_1") (pintype "passive"))
      (node (ref "R3") (pin "1") (pinfunction "1_1") (pintype "passive"))
      (node (ref "R4") (pin "1") (pinfunction "1_1") (pintype "passive"))
    )
    (net (code "36") (name "unconnected-(U1-NC-Pad1)") (class "Default")
      (node (ref "U1") (pin "1") (pinfunction "NC_1") (pintype "passive"))
    )
    (net (code "37") (name "unconnected-(U1-NC-Pad2)") (class "Default")
      (node (ref "U1") (pin "2") (pinfunction "NC_2") (pintype "passive"))
    )
    (net (code "38") (name "unconnected-(U3-OSCIN{slash}PA1-Pad2)") (class "Default")
      (node (ref "U3") (pin "2") (pinfunction "OSCIN/PA1_2") (pintype "passive"))
    )
    (net (code "39") (name "unconnected-(U3-OSCOUT{slash}PA2-Pad3)") (class "Default")
      (node (ref "U3") (pin "3") (pinfunction "OSCOUT/PA2_3") (pintype "passive"))
    )
    (net (code "40") (name "unconnected-(U3-PA3-Pad7)") (class "Default")
      (node (ref "U3") (pin "7") (pinfunction "PA3_7") (pintype "passive"))
    )
    (net (code "41") (name "unconnected-(U3-PB4-Pad9)") (class "Default")
      (node (ref "U3") (pin "9") (pinfunction "PB4_9") (pintype "passive"))
    )
    (net (code "42") (name "unconnected-(U3-PB5-Pad8)") (class "Default")
      (node (ref "U3") (pin "8") (pinfunction "PB5_8") (pintype "passive"))
    )
    (net (code "43") (name "unconnected-(U3-PC3-Pad10)") (class "Default")
      (node (ref "U3") (pin "10") (pinfunction "PC3_10") (pintype "passive"))
    )
    (net (code "44") (name "unconnected-(U3-PC7-Pad14)") (class "Default")
      (node (ref "U3") (pin "14") (pinfunction "PC7_14") (pintype "passive"))
    )
    (net (code "45") (name "unconnected-(U3-PD2-Pad16)") (class "Default")
      (node (ref "U3") (pin "16") (pinfunction "PD2_16") (pintype "passive"))
    )
    (net (code "46") (name "unconnected-(U3-PD3-Pad17)") (class "Default")
      (node (ref "U3") (pin "17") (pinfunction "PD3_17") (pintype "passive"))
    )
    (net (code "47") (name "unconnected-(U3-PD4-Pad18)") (class "Default")
      (node (ref "U3") (pin "18") (pinfunction "PD4_18") (pintype "passive"))
    )
  )
)
